# Microcontroller.net
KiCad netlist of a schematic drawn in Altium Designer
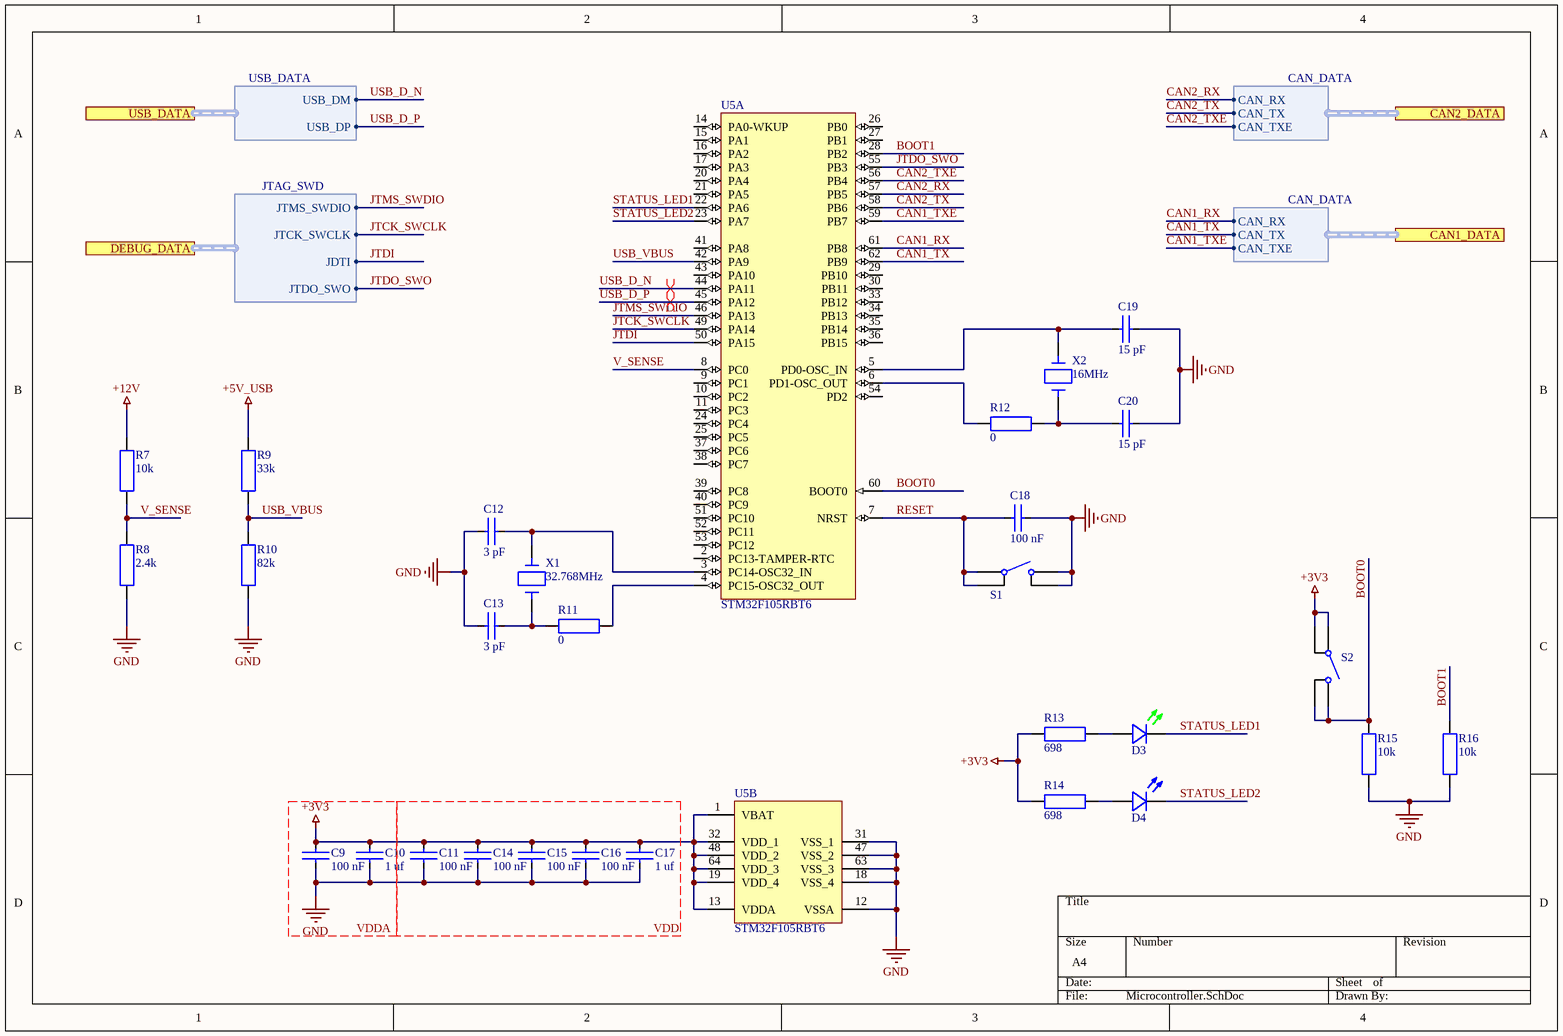
[diagram p0: Microcontroller.SchDoc]

(export (version "E")
  (design (tool "Eeschema 10.0.6"))
  (components
    (comp (ref "C9")
      (value "100 nF")
      (footprint "0603 SMD CAP")
      (description "25V 100nF X7R ±10% 0603 Multilayer Ceramic Capacitors MLCC")
      (fields (field (name "PART NUMBER") "CL10B104KA8NNNC"))
      (libsource (lib "Max_lib") (part "Cap 100nF 0603"))
    )
    (comp (ref "C10")
      (value "1 uf")
      (footprint "0603 SMD CAP")
      (description "25V 1uF X5R ±10% 0603 Multilayer Ceramic Capacitors MLCC")
      (fields (field (name "PART NUMBER") "CC0603KRX5R8BB105"))
      (libsource (lib "Max_lib") (part "Cap 1u 0603"))
    )
    (comp (ref "C11")
      (value "100 nF")
      (footprint "0603 SMD CAP")
      (description "25V 100nF X7R ±10% 0603 Multilayer Ceramic Capacitors MLCC")
      (fields (field (name "PART NUMBER") "CL10B104KA8NNNC"))
      (libsource (lib "Max_lib") (part "Cap 100nF 0603"))
    )
    (comp (ref "C12")
      (value "3 pF")
      (footprint "0603 SMD CAP")
      (description "50V 3pF NP0 0.25pF 0603 Multilayer Ceramic Capacitors MLCC")
      (fields (field (name "PART NUMBER") "CC0603JRNPO9BN100"))
      (libsource (lib "Max_lib") (part "Cap 3pF 0603"))
    )
    (comp (ref "C13")
      (value "3 pF")
      (footprint "0603 SMD CAP")
      (description "50V 3pF NP0 0.25pF 0603 Multilayer Ceramic Capacitors MLCC")
      (fields (field (name "PART NUMBER") "CC0603JRNPO9BN100"))
      (libsource (lib "Max_lib") (part "Cap 3pF 0603"))
    )
    (comp (ref "C14")
      (value "100 nF")
      (footprint "0603 SMD CAP")
      (description "25V 100nF X7R ±10% 0603 Multilayer Ceramic Capacitors MLCC")
      (fields (field (name "PART NUMBER") "CL10B104KA8NNNC"))
      (libsource (lib "Max_lib") (part "Cap 100nF 0603"))
    )
    (comp (ref "C15")
      (value "100 nF")
      (footprint "0603 SMD CAP")
      (description "25V 100nF X7R ±10% 0603 Multilayer Ceramic Capacitors MLCC")
      (fields (field (name "PART NUMBER") "CL10B104KA8NNNC"))
      (libsource (lib "Max_lib") (part "Cap 100nF 0603"))
    )
    (comp (ref "C16")
      (value "100 nF")
      (footprint "0603 SMD CAP")
      (description "25V 100nF X7R ±10% 0603 Multilayer Ceramic Capacitors MLCC")
      (fields (field (name "PART NUMBER") "CL10B104KA8NNNC"))
      (libsource (lib "Max_lib") (part "Cap 100nF 0603"))
    )
    (comp (ref "C17")
      (value "1 uf")
      (footprint "0603 SMD CAP")
      (description "25V 1uF X5R ±10% 0603 Multilayer Ceramic Capacitors MLCC")
      (fields (field (name "PART NUMBER") "CC0603KRX5R8BB105"))
      (libsource (lib "Max_lib") (part "Cap 1u 0603"))
    )
    (comp (ref "C18")
      (value "100 nF")
      (footprint "0603 SMD CAP")
      (description "25V 100nF X7R ±10% 0603 Multilayer Ceramic Capacitors MLCC")
      (fields (field (name "PART NUMBER") "CL10B104KA8NNNC"))
      (libsource (lib "Max_lib") (part "Cap 100nF 0603"))
    )
    (comp (ref "C19")
      (value "15 pF")
      (footprint "0603 SMD CAP")
      (description "50V 15pF NP0 ±5% 0603 Multilayer Ceramic Capacitors MLCC")
      (fields (field (name "PART NUMBER") "CC0603JRNPO9BN100"))
      (libsource (lib "Max_lib") (part "Cap 15pF 0603"))
    )
    (comp (ref "C20")
      (value "15 pF")
      (footprint "0603 SMD CAP")
      (description "50V 15pF NP0 ±5% 0603 Multilayer Ceramic Capacitors MLCC")
      (fields (field (name "PART NUMBER") "CC0603JRNPO9BN100"))
      (libsource (lib "Max_lib") (part "Cap 15pF 0603"))
    )
    (comp (ref "D3")
      (value "LED Green 0603")
      (footprint "0603 SMD LED")
      (description "20mA 518nm Colorless transparence -40℃~+85℃ 520nm~535nm Emerald 120° 110mW 0603")
      (fields (field (name "PART NUMBER") "19-217/GHC-YR1S2/3T"))
      (libsource (lib "Max_lib") (part "LED Green 0603"))
    )
    (comp (ref "D4")
      (value "LED Blue 0603")
      (footprint "0603 SMD LED")
      (description "25mA Green -30℃~+85℃ Positive post Blue 120° 80mW 0603")
      (fields (field (name "PART NUMBER") "XL-1608BGWC-06"))
      (libsource (lib "Max_lib") (part "LED Blue 0603"))
    )
    (comp (ref "R7")
      (value "10k")
      (footprint "0603 SMD Res")
      (description "Resistor 10k 0603 1%")
      (fields (field (name "PART NUMBER") "RC0603FR-0710KL"))
      (libsource (lib "Max_lib") (part "Resistor 10k 0603 1%"))
    )
    (comp (ref "R8")
      (value "2.4k")
      (footprint "0603 SMD Res")
      (description "100mW Thick Film Resistors 75V ±100ppm/℃ ±1% -55℃~+155℃ 2.4kΩ 0603 Chip Resistor")
      (fields (field (name "PART NUMBER") "RC0603FR-072K4L"))
      (libsource (lib "Max_lib") (part "Resistor 2.4k 0603 1%"))
    )
    (comp (ref "R9")
      (value "33k")
      (footprint "0603 SMD Res")
      (description "100mW Thin Film Resistor 75V ±25ppm/℃ ±1% -55℃~+155℃ 33kΩ 0603 Chip Resistor")
      (fields (field (name "PART NUMBER") "ARG03FTC3302"))
      (libsource (lib "Max_lib") (part "Resistor 33k 0603"))
    )
    (comp (ref "R10")
      (value "82k")
      (footprint "0603 SMD Res")
      (description "100mW Thick Film Resistors 50V ±100ppm/℃ ±1% -55℃~+155℃ 82kΩ 0603 Chip Resistor")
      (fields (field (name "PART NUMBER") "FRC0603F8202TS"))
      (libsource (lib "Max_lib") (part "Resistor 82k 0603"))
    )
    (comp (ref "R11")
      (value "0")
      (footprint "0603 SMD Res")
      (description "Thick Film Resistors -55℃~+155℃ 0Ω 0603 Chip Resistor")
      (fields (field (name "PART NUMBER") "FRC0603P000 TS"))
      (libsource (lib "Max_lib") (part "Resistor 0 0603"))
    )
    (comp (ref "R12")
      (value "0")
      (footprint "0603 SMD Res")
      (description "Thick Film Resistors -55℃~+155℃ 0Ω 0603 Chip Resistor")
      (fields (field (name "PART NUMBER") "FRC0603P000 TS"))
      (libsource (lib "Max_lib") (part "Resistor 0 0603"))
    )
    (comp (ref "R13")
      (value "698")
      (footprint "0603 SMD Res")
      (description "100mW Thick Film Resistors 75V ±100ppm/℃ ±1% -55℃~+155℃ 698Ω 0603 Chip Resistor")
      (fields (field (name "PART NUMBER") "AC0603FR-07698RL"))
      (libsource (lib "Max_lib") (part "Resistor 698 0603 1%"))
    )
    (comp (ref "R14")
      (value "698")
      (footprint "0603 SMD Res")
      (description "100mW Thick Film Resistors 75V ±100ppm/℃ ±1% -55℃~+155℃ 698Ω 0603 Chip Resistor")
      (fields (field (name "PART NUMBER") "AC0603FR-07698RL"))
      (libsource (lib "Max_lib") (part "Resistor 698 0603 1%"))
    )
    (comp (ref "R15")
      (value "10k")
      (footprint "0603 SMD Res")
      (description "Resistor 10k 0603 1%")
      (fields (field (name "PART NUMBER") "RC0603FR-0710KL"))
      (libsource (lib "Max_lib") (part "Resistor 10k 0603 1%"))
    )
    (comp (ref "R16")
      (value "10k")
      (footprint "0603 SMD Res")
      (description "Resistor 10k 0603 1%")
      (fields (field (name "PART NUMBER") "RC0603FR-0710KL"))
      (libsource (lib "Max_lib") (part "Resistor 10k 0603 1%"))
    )
    (comp (ref "S1")
      (value "Tactile SPST Switch")
      (footprint "Tactile Switch 4.2x3.4")
      (fields (field (name "PART NUMBER") "YTSA016C0254004B"))
      (libsource (lib "Max_lib") (part "Tactile SPST Switch"))
    )
    (comp (ref "S2")
      (value "Tactile SPST Switch")
      (footprint "Tactile Switch 4.2x3.4")
      (fields (field (name "PART NUMBER") "YTSA016C0254004B"))
      (libsource (lib "Max_lib") (part "Tactile SPST Switch"))
    )
    (comp (ref "U5")
      (value "STM32F105RBT6")
      (footprint "STM-LQFP64_V")
      (libsource (lib "Altium Content Vault") (part "MC-ARM-STM32F10X-SQ64"))
    )
    (comp (ref "X1")
      (value "32.768MHz")
      (footprint "3215 SMD CRYSTAL")
      (description "32.768kHz 6pF 70kΩ ±20ppm -40℃~+85℃ SMD3215-2P Crystals ROHS")
      (fields (field (name "PART NUMBER") "NX3215SA-32.768K-STD-MUA-14"))
      (libsource (lib "Max_lib") (part "Crystal 32.768MHz SMD"))
    )
    (comp (ref "X2")
      (value "16MHz")
      (footprint "3225 SMD Crystal")
      (description "Crystal 16MHz 12pf")
      (libsource (lib "Max_lib") (part "Crystal 16MHz 3225"))
    )
  )
  (nets
    (net (code "4") (name "+3V3") (class "Default")
      (node (ref "C10") (pin "2") (pinfunction "2_2") (pintype "passive"))
      (node (ref "C11") (pin "2") (pinfunction "2_2") (pintype "passive"))
      (node (ref "C14") (pin "2") (pinfunction "2_2") (pintype "passive"))
      (node (ref "C15") (pin "2") (pinfunction "2_2") (pintype "passive"))
      (node (ref "C16") (pin "2") (pinfunction "2_2") (pintype "passive"))
      (node (ref "C17") (pin "2") (pinfunction "2_2") (pintype "passive"))
      (node (ref "C9") (pin "2") (pinfunction "2_2") (pintype "passive"))
      (node (ref "R13") (pin "2") (pinfunction "2_2") (pintype "passive"))
      (node (ref "R14") (pin "2") (pinfunction "2_2") (pintype "passive"))
      (node (ref "S2") (pin "1") (pinfunction "1_1") (pintype "passive"))
      (node (ref "S2") (pin "2") (pinfunction "2_2") (pintype "passive"))
      (node (ref "U5") (pin "1") (pinfunction "VBAT_1") (pintype "power_in"))
      (node (ref "U5") (pin "13") (pinfunction "VDDA_13") (pintype "power_in"))
      (node (ref "U5") (pin "19") (pinfunction "VDD_4_19") (pintype "power_in"))
      (node (ref "U5") (pin "32") (pinfunction "VDD_1_32") (pintype "power_in"))
      (node (ref "U5") (pin "48") (pinfunction "VDD_2_48") (pintype "power_in"))
      (node (ref "U5") (pin "64") (pinfunction "VDD_3_64") (pintype "power_in"))
    )
    (net (code "5") (name "+5V_USB") (class "Default")
      (node (ref "R9") (pin "2") (pinfunction "2_2") (pintype "passive"))
    )
    (net (code "6") (name "+12V") (class "Default")
      (node (ref "R7") (pin "2") (pinfunction "2_2") (pintype "passive"))
    )
    (net (code "7") (name "/BOOT0") (class "Default")
      (node (ref "R15") (pin "2") (pinfunction "2_2") (pintype "passive"))
      (node (ref "S2") (pin "3") (pinfunction "3_3") (pintype "passive"))
      (node (ref "S2") (pin "4") (pinfunction "4_4") (pintype "passive"))
      (node (ref "U5") (pin "60") (pinfunction "BOOT0_60") (pintype "input"))
    )
    (net (code "8") (name "/BOOT1") (class "Default")
      (node (ref "R16") (pin "2") (pinfunction "2_2") (pintype "passive"))
      (node (ref "U5") (pin "28") (pinfunction "PB2_28") (pintype "bidirectional"))
    )
    (net (code "9") (name "/CAN1_RX") (class "Default")
      (node (ref "U5") (pin "61") (pinfunction "PB8_61") (pintype "bidirectional"))
    )
    (net (code "10") (name "/CAN1_TX") (class "Default")
      (node (ref "U5") (pin "62") (pinfunction "PB9_62") (pintype "bidirectional"))
    )
    (net (code "11") (name "/CAN1_TXE") (class "Default")
      (node (ref "U5") (pin "59") (pinfunction "PB7_59") (pintype "bidirectional"))
    )
    (net (code "12") (name "/CAN2_RX") (class "Default")
      (node (ref "U5") (pin "57") (pinfunction "PB5_57") (pintype "bidirectional"))
    )
    (net (code "13") (name "/CAN2_TX") (class "Default")
      (node (ref "U5") (pin "58") (pinfunction "PB6_58") (pintype "bidirectional"))
    )
    (net (code "14") (name "/CAN2_TXE") (class "Default")
      (node (ref "U5") (pin "56") (pinfunction "PB4_56") (pintype "bidirectional"))
    )
    (net (code "15") (name "/JTCK_SWCLK") (class "Default")
      (node (ref "U5") (pin "49") (pinfunction "PA14_49") (pintype "bidirectional"))
    )
    (net (code "16") (name "/JTDI") (class "Default")
      (node (ref "U5") (pin "50") (pinfunction "PA15_50") (pintype "bidirectional"))
    )
    (net (code "17") (name "/JTDO_SWO") (class "Default")
      (node (ref "U5") (pin "55") (pinfunction "PB3_55") (pintype "bidirectional"))
    )
    (net (code "18") (name "/JTMS_SWDIO") (class "Default")
      (node (ref "U5") (pin "46") (pinfunction "PA13_46") (pintype "bidirectional"))
    )
    (net (code "19") (name "/RESET") (class "Default")
      (node (ref "C18") (pin "1") (pinfunction "1_1") (pintype "passive"))
      (node (ref "S1") (pin "1") (pinfunction "1_1") (pintype "passive"))
      (node (ref "S1") (pin "2") (pinfunction "2_2") (pintype "passive"))
      (node (ref "U5") (pin "7") (pinfunction "NRST_7") (pintype "bidirectional"))
    )
    (net (code "20") (name "/STATUS_LED1") (class "Default")
      (node (ref "D3") (pin "2") (pinfunction "2_2") (pintype "passive"))
      (node (ref "U5") (pin "22") (pinfunction "PA6_22") (pintype "bidirectional"))
    )
    (net (code "21") (name "/STATUS_LED2") (class "Default")
      (node (ref "D4") (pin "2") (pinfunction "2_2") (pintype "passive"))
      (node (ref "U5") (pin "23") (pinfunction "PA7_23") (pintype "bidirectional"))
    )
    (net (code "22") (name "/USB_D_N") (class "Default")
      (node (ref "U5") (pin "44") (pinfunction "PA11_44") (pintype "bidirectional"))
    )
    (net (code "23") (name "/USB_D_P") (class "Default")
      (node (ref "U5") (pin "45") (pinfunction "PA12_45") (pintype "bidirectional"))
    )
    (net (code "24") (name "/USB_VBUS") (class "Default")
      (node (ref "R10") (pin "2") (pinfunction "2_2") (pintype "passive"))
      (node (ref "R9") (pin "1") (pinfunction "1_1") (pintype "passive"))
      (node (ref "U5") (pin "42") (pinfunction "PA9_42") (pintype "bidirectional"))
    )
    (net (code "25") (name "/V_SENSE") (class "Default")
      (node (ref "R7") (pin "1") (pinfunction "1_1") (pintype "passive"))
      (node (ref "R8") (pin "2") (pinfunction "2_2") (pintype "passive"))
      (node (ref "U5") (pin "8") (pinfunction "PC0_8") (pintype "bidirectional"))
    )
    (net (code "29") (name "GND") (class "Default")
      (node (ref "C10") (pin "1") (pinfunction "1_1") (pintype "passive"))
      (node (ref "C11") (pin "1") (pinfunction "1_1") (pintype "passive"))
      (node (ref "C12") (pin "1") (pinfunction "1_1") (pintype "passive"))
      (node (ref "C13") (pin "1") (pinfunction "1_1") (pintype "passive"))
      (node (ref "C14") (pin "1") (pinfunction "1_1") (pintype "passive"))
      (node (ref "C15") (pin "1") (pinfunction "1_1") (pintype "passive"))
      (node (ref "C16") (pin "1") (pinfunction "1_1") (pintype "passive"))
      (node (ref "C17") (pin "1") (pinfunction "1_1") (pintype "passive"))
      (node (ref "C18") (pin "2") (pinfunction "2_2") (pintype "passive"))
      (node (ref "C19") (pin "2") (pinfunction "2_2") (pintype "passive"))
      (node (ref "C20") (pin "2") (pinfunction "2_2") (pintype "passive"))
      (node (ref "C9") (pin "1") (pinfunction "1_1") (pintype "passive"))
      (node (ref "R10") (pin "1") (pinfunction "1_1") (pintype "passive"))
      (node (ref "R15") (pin "1") (pinfunction "1_1") (pintype "passive"))
      (node (ref "R16") (pin "1") (pinfunction "1_1") (pintype "passive"))
      (node (ref "R8") (pin "1") (pinfunction "1_1") (pintype "passive"))
      (node (ref "S1") (pin "3") (pinfunction "3_3") (pintype "passive"))
      (node (ref "S1") (pin "4") (pinfunction "4_4") (pintype "passive"))
      (node (ref "U5") (pin "12") (pinfunction "VSSA_12") (pintype "power_in"))
      (node (ref "U5") (pin "18") (pinfunction "VSS_4_18") (pintype "power_in"))
      (node (ref "U5") (pin "31") (pinfunction "VSS_1_31") (pintype "power_in"))
      (node (ref "U5") (pin "47") (pinfunction "VSS_2_47") (pintype "power_in"))
      (node (ref "U5") (pin "63") (pinfunction "VSS_3_63") (pintype "power_in"))
    )
    (net (code "30") (name "Net-(C13-Pad2)") (class "Default")
      (node (ref "C13") (pin "2") (pinfunction "2_2") (pintype "passive"))
      (node (ref "R11") (pin "2") (pinfunction "2_2") (pintype "passive"))
      (node (ref "X1") (pin "1") (pinfunction "1_1") (pintype "passive"))
    )
    (net (code "31") (name "Net-(C20-Pad1)") (class "Default")
      (node (ref "C20") (pin "1") (pinfunction "1_1") (pintype "passive"))
      (node (ref "R12") (pin "1") (pinfunction "1_1") (pintype "passive"))
      (node (ref "X2") (pin "1") (pinfunction "1_1") (pintype "passive"))
    )
    (net (code "32") (name "Net-(D3-Pad1)") (class "Default")
      (node (ref "D3") (pin "1") (pinfunction "1_1") (pintype "passive"))
      (node (ref "R13") (pin "1") (pinfunction "1_1") (pintype "passive"))
    )
    (net (code "33") (name "Net-(D4-Pad1)") (class "Default")
      (node (ref "D4") (pin "1") (pinfunction "1_1") (pintype "passive"))
      (node (ref "R14") (pin "1") (pinfunction "1_1") (pintype "passive"))
    )
    (net (code "34") (name "Net-(U5A-PC14-OSC32_IN)") (class "Default")
      (node (ref "C12") (pin "2") (pinfunction "2_2") (pintype "passive"))
      (node (ref "U5") (pin "3") (pinfunction "PC14-OSC32_IN_3") (pintype "bidirectional"))
      (node (ref "X1") (pin "2") (pinfunction "2_2") (pintype "passive"))
    )
    (net (code "35") (name "Net-(U5A-PC15-OSC32_OUT)") (class "Default")
      (node (ref "R11") (pin "1") (pinfunction "1_1") (pintype "passive"))
      (node (ref "U5") (pin "4") (pinfunction "PC15-OSC32_OUT_4") (pintype "bidirectional"))
    )
    (net (code "36") (name "Net-(U5A-PD0-OSC_IN)") (class "Default")
      (node (ref "C19") (pin "1") (pinfunction "1_1") (pintype "passive"))
      (node (ref "U5") (pin "5") (pinfunction "PD0-OSC_IN_5") (pintype "bidirectional"))
      (node (ref "X2") (pin "3") (pinfunction "3_3") (pintype "passive"))
    )
    (net (code "37") (name "Net-(U5A-PD1-OSC_OUT)") (class "Default")
      (node (ref "R12") (pin "2") (pinfunction "2_2") (pintype "passive"))
      (node (ref "U5") (pin "6") (pinfunction "PD1-OSC_OUT_6") (pintype "bidirectional"))
    )
    (net (code "38") (name "unconnected-(U5A-PA0-WKUP-Pad14)") (class "Default")
      (node (ref "U5") (pin "14") (pinfunction "PA0-WKUP_14") (pintype "bidirectional"))
    )
    (net (code "39") (name "unconnected-(U5A-PA1-Pad15)") (class "Default")
      (node (ref "U5") (pin "15") (pinfunction "PA1_15") (pintype "bidirectional"))
    )
    (net (code "40") (name "unconnected-(U5A-PA2-Pad16)") (class "Default")
      (node (ref "U5") (pin "16") (pinfunction "PA2_16") (pintype "bidirectional"))
    )
    (net (code "41") (name "unconnected-(U5A-PA3-Pad17)") (class "Default")
      (node (ref "U5") (pin "17") (pinfunction "PA3_17") (pintype "bidirectional"))
    )
    (net (code "42") (name "unconnected-(U5A-PA4-Pad20)") (class "Default")
      (node (ref "U5") (pin "20") (pinfunction "PA4_20") (pintype "bidirectional"))
    )
    (net (code "43") (name "unconnected-(U5A-PA5-Pad21)") (class "Default")
      (node (ref "U5") (pin "21") (pinfunction "PA5_21") (pintype "bidirectional"))
    )
    (net (code "44") (name "unconnected-(U5A-PA8-Pad41)") (class "Default")
      (node (ref "U5") (pin "41") (pinfunction "PA8_41") (pintype "bidirectional"))
    )
    (net (code "45") (name "unconnected-(U5A-PA10-Pad43)") (class "Default")
      (node (ref "U5") (pin "43") (pinfunction "PA10_43") (pintype "bidirectional"))
    )
    (net (code "46") (name "unconnected-(U5A-PB0-Pad26)") (class "Default")
      (node (ref "U5") (pin "26") (pinfunction "PB0_26") (pintype "bidirectional"))
    )
    (net (code "47") (name "unconnected-(U5A-PB1-Pad27)") (class "Default")
      (node (ref "U5") (pin "27") (pinfunction "PB1_27") (pintype "bidirectional"))
    )
    (net (code "48") (name "unconnected-(U5A-PB10-Pad29)") (class "Default")
      (node (ref "U5") (pin "29") (pinfunction "PB10_29") (pintype "bidirectional"))
    )
    (net (code "49") (name "unconnected-(U5A-PB11-Pad30)") (class "Default")
      (node (ref "U5") (pin "30") (pinfunction "PB11_30") (pintype "bidirectional"))
    )
    (net (code "50") (name "unconnected-(U5A-PB12-Pad33)") (class "Default")
      (node (ref "U5") (pin "33") (pinfunction "PB12_33") (pintype "bidirectional"))
    )
    (net (code "51") (name "unconnected-(U5A-PB13-Pad34)") (class "Default")
      (node (ref "U5") (pin "34") (pinfunction "PB13_34") (pintype "bidirectional"))
    )
    (net (code "52") (name "unconnected-(U5A-PB14-Pad35)") (class "Default")
      (node (ref "U5") (pin "35") (pinfunction "PB14_35") (pintype "bidirectional"))
    )
    (net (code "53") (name "unconnected-(U5A-PB15-Pad36)") (class "Default")
      (node (ref "U5") (pin "36") (pinfunction "PB15_36") (pintype "bidirectional"))
    )
    (net (code "54") (name "unconnected-(U5A-PC1-Pad9)") (class "Default")
      (node (ref "U5") (pin "9") (pinfunction "PC1_9") (pintype "bidirectional"))
    )
    (net (code "55") (name "unconnected-(U5A-PC2-Pad10)") (class "Default")
      (node (ref "U5") (pin "10") (pinfunction "PC2_10") (pintype "bidirectional"))
    )
    (net (code "56") (name "unconnected-(U5A-PC3-Pad11)") (class "Default")
      (node (ref "U5") (pin "11") (pinfunction "PC3_11") (pintype "bidirectional"))
    )
    (net (code "57") (name "unconnected-(U5A-PC4-Pad24)") (class "Default")
      (node (ref "U5") (pin "24") (pinfunction "PC4_24") (pintype "bidirectional"))
    )
    (net (code "58") (name "unconnected-(U5A-PC5-Pad25)") (class "Default")
      (node (ref "U5") (pin "25") (pinfunction "PC5_25") (pintype "bidirectional"))
    )
    (net (code "59") (name "unconnected-(U5A-PC6-Pad37)") (class "Default")
      (node (ref "U5") (pin "37") (pinfunction "PC6_37") (pintype "bidirectional"))
    )
    (net (code "60") (name "unconnected-(U5A-PC7-Pad38)") (class "Default")
      (node (ref "U5") (pin "38") (pinfunction "PC7_38") (pintype "bidirectional"))
    )
    (net (code "61") (name "unconnected-(U5A-PC8-Pad39)") (class "Default")
      (node (ref "U5") (pin "39") (pinfunction "PC8_39") (pintype "bidirectional"))
    )
    (net (code "62") (name "unconnected-(U5A-PC9-Pad40)") (class "Default")
      (node (ref "U5") (pin "40") (pinfunction "PC9_40") (pintype "bidirectional"))
    )
    (net (code "63") (name "unconnected-(U5A-PC10-Pad51)") (class "Default")
      (node (ref "U5") (pin "51") (pinfunction "PC10_51") (pintype "bidirectional"))
    )
    (net (code "64") (name "unconnected-(U5A-PC11-Pad52)") (class "Default")
      (node (ref "U5") (pin "52") (pinfunction "PC11_52") (pintype "bidirectional"))
    )
    (net (code "65") (name "unconnected-(U5A-PC12-Pad53)") (class "Default")
      (node (ref "U5") (pin "53") (pinfunction "PC12_53") (pintype "bidirectional"))
    )
    (net (code "66") (name "unconnected-(U5A-PC13-TAMPER-RTC-Pad2)") (class "Default")
      (node (ref "U5") (pin "2") (pinfunction "PC13-TAMPER-RTC_2") (pintype "bidirectional"))
    )
    (net (code "67") (name "unconnected-(U5A-PD2-Pad54)") (class "Default")
      (node (ref "U5") (pin "54") (pinfunction "PD2_54") (pintype "bidirectional"))
    )
  )
)
